# neoPeak.net
KiCad netlist of a schematic drawn in Altium Designer
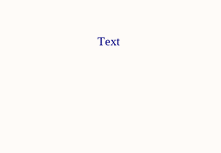
[diagram p0: neoPeak.SchDoc, top middle]
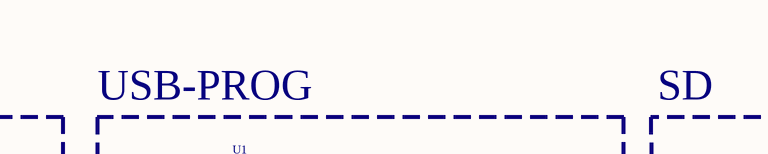
[diagram p1: neoPeak.SchDoc, top right]
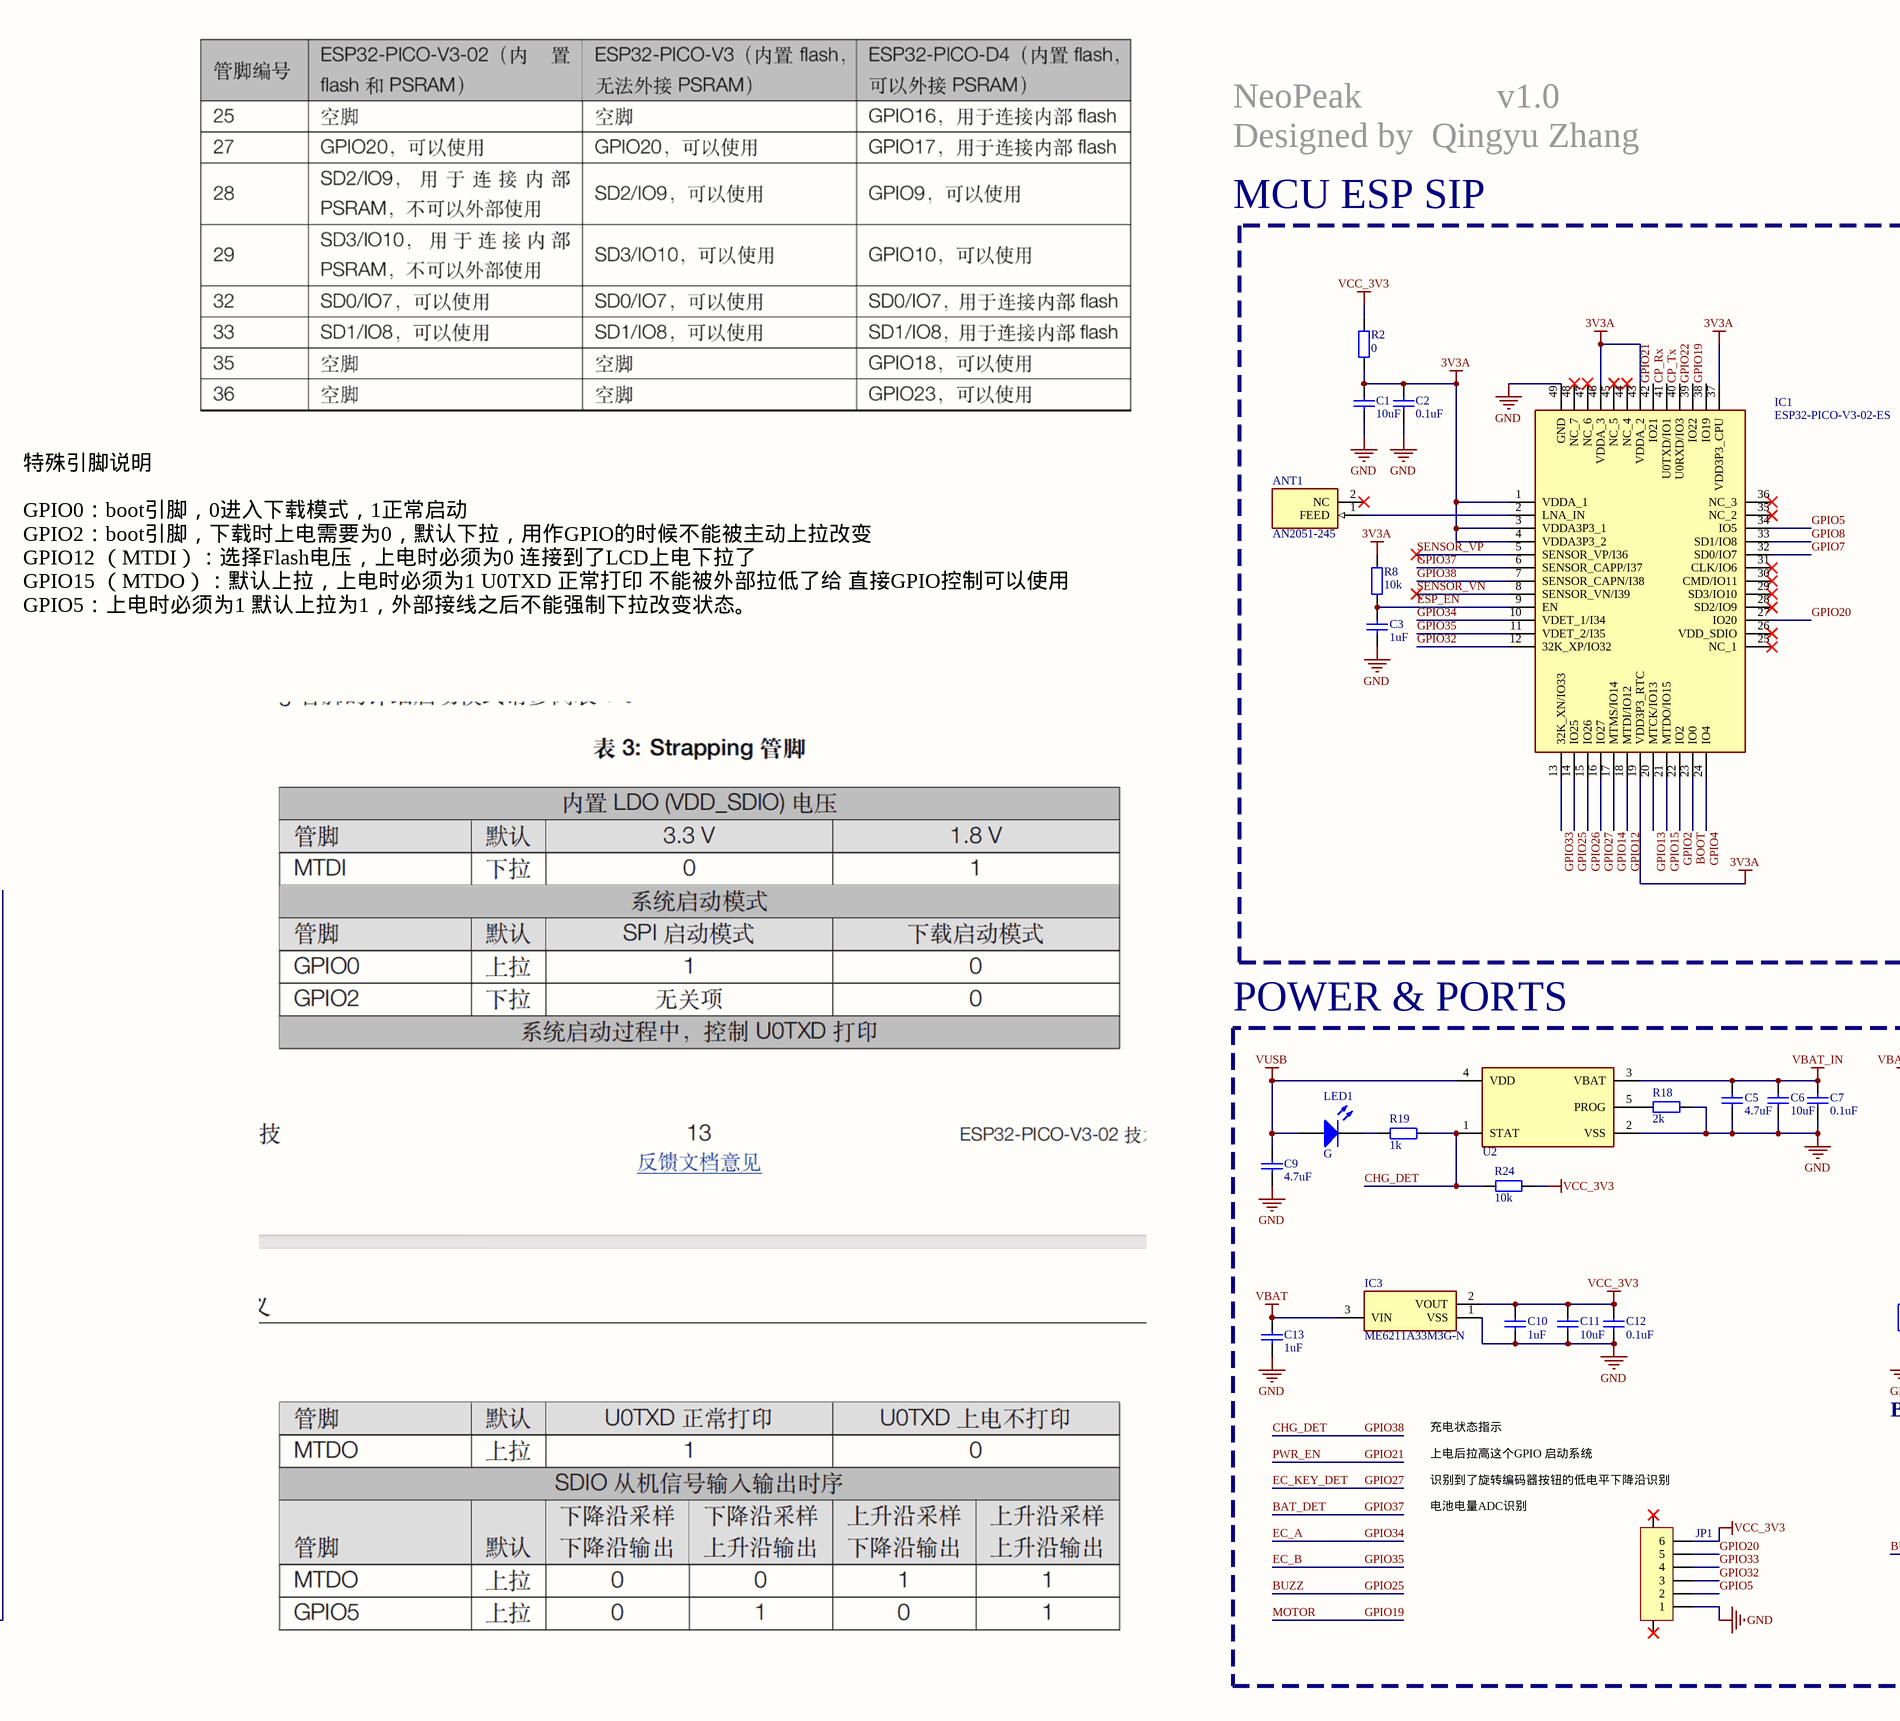
[diagram p2: neoPeak.SchDoc, bottom middle]
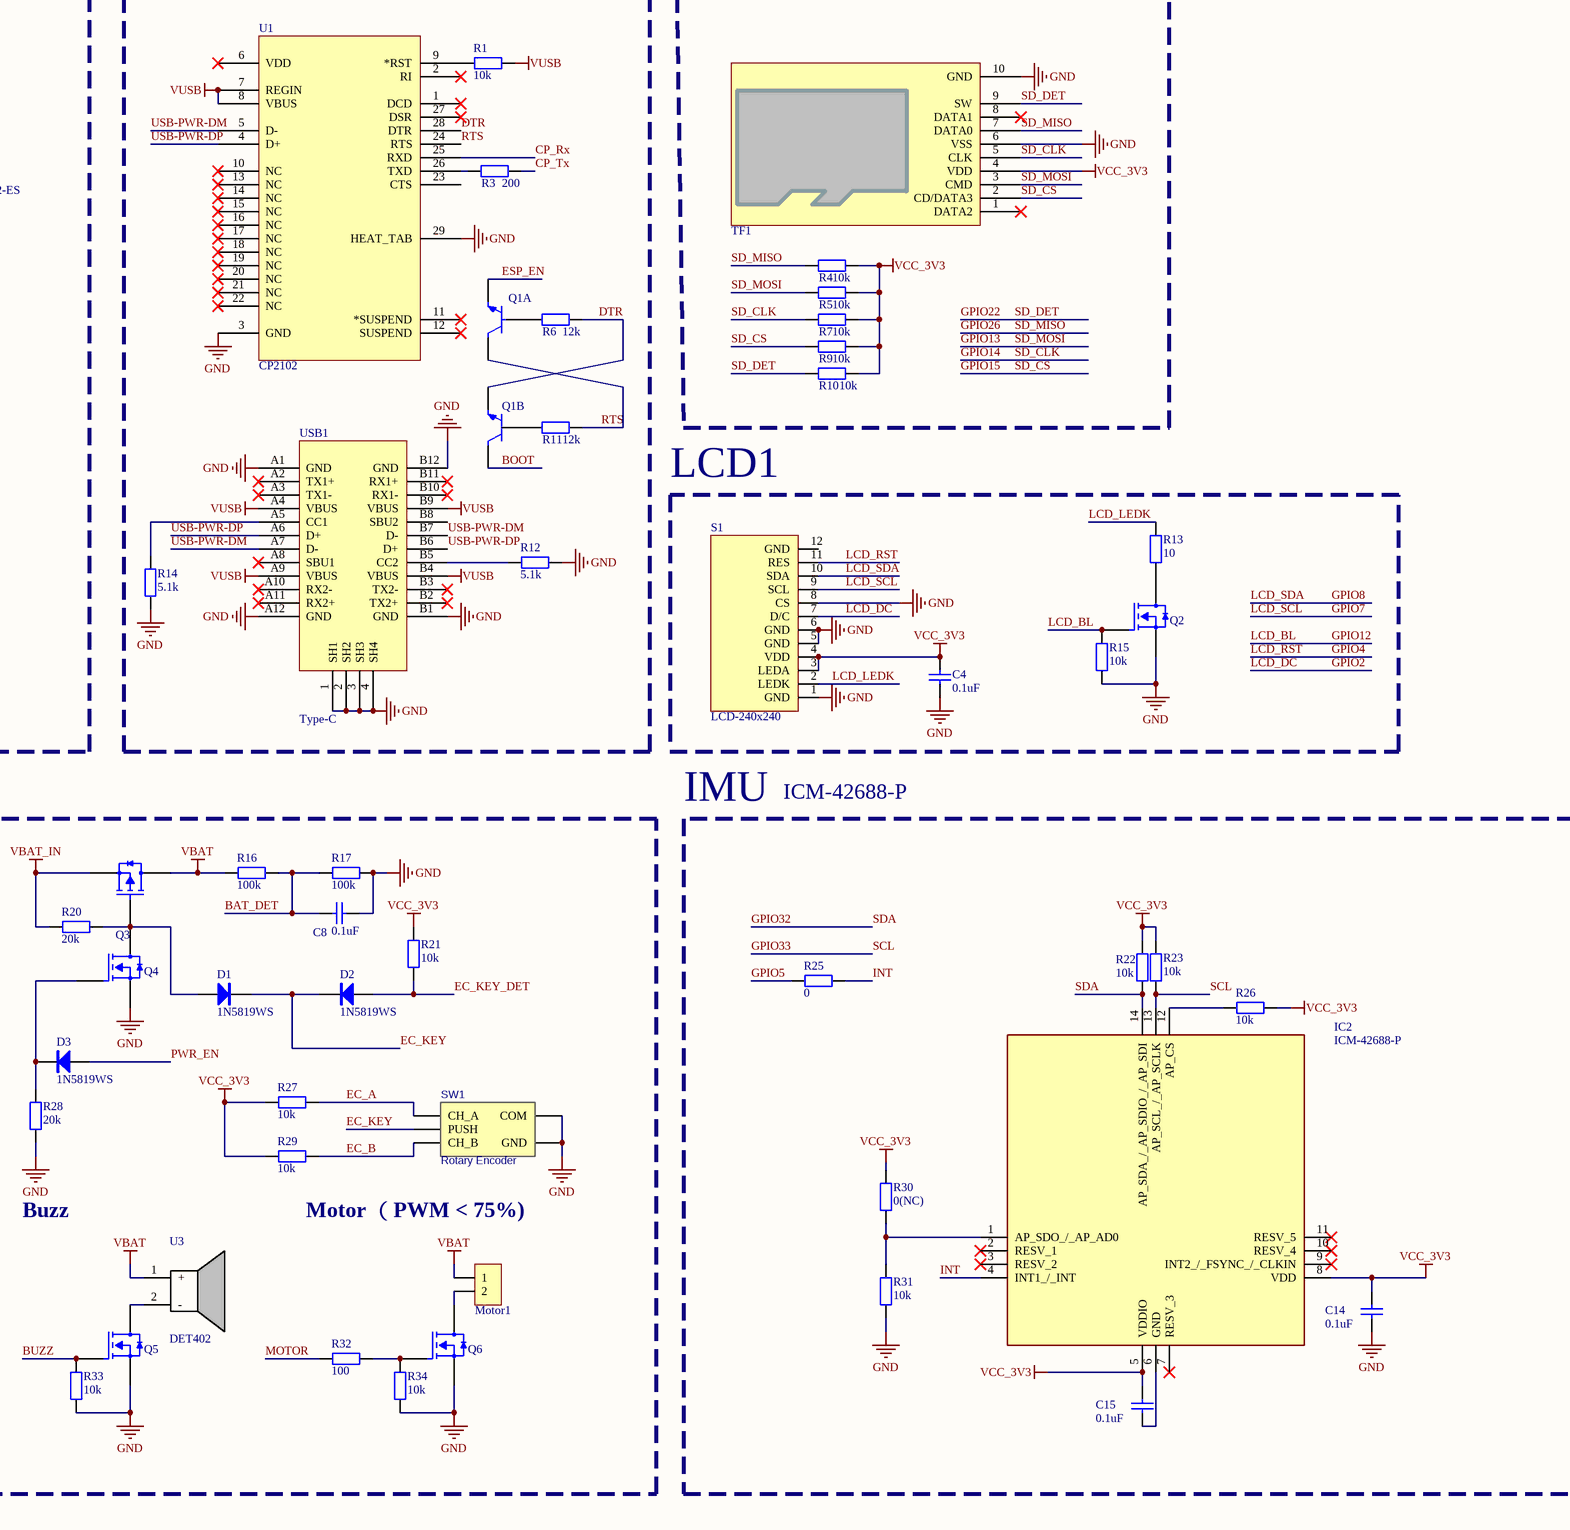
[diagram p3: neoPeak.SchDoc, bottom right]

(export (version "E")
  (design (tool "Eeschema 10.0.6"))
  (components
    (comp (ref "ANT1")
      (value "AN2051-245")
      (footprint "SamacSys:ANTC5020X127N")
      (description "Antenna")
      (libsource (lib "*") (part "AN2051-245"))
    )
    (comp (ref "C1")
      (value "10uF")
      (footprint "C0402_L")
      (description "贴片电容/MLCC电容")
      (libsource (lib "0.1 - 电阻-电容-电感-保险丝-晶振-晶体-磁珠-电位器-法拉电容-馈通电容") (part "C"))
    )
    (comp (ref "C2")
      (value "0.1uF")
      (footprint "C0402_L")
      (description "贴片电容/MLCC电容")
      (libsource (lib "0.1 - 电阻-电容-电感-保险丝-晶振-晶体-磁珠-电位器-法拉电容-馈通电容") (part "C"))
    )
    (comp (ref "C3")
      (value "1uF")
      (footprint "C0402_L")
      (description "贴片电容/MLCC电容")
      (libsource (lib "0.1 - 电阻-电容-电感-保险丝-晶振-晶体-磁珠-电位器-法拉电容-馈通电容") (part "C"))
    )
    (comp (ref "C4")
      (value "0.1uF")
      (footprint "C0402_L")
      (description "贴片电容/MLCC电容")
      (libsource (lib "0.1 - 电阻-电容-电感-保险丝-晶振-晶体-磁珠-电位器-法拉电容-馈通电容") (part "C"))
    )
    (comp (ref "C5")
      (value "4.7uF")
      (footprint "C0402_L")
      (description "贴片电容/MLCC电容")
      (libsource (lib "0.1 - 电阻-电容-电感-保险丝-晶振-晶体-磁珠-电位器-法拉电容-馈通电容") (part "C"))
    )
    (comp (ref "C6")
      (value "10uF")
      (footprint "C0402_L")
      (description "贴片电容/MLCC电容")
      (libsource (lib "0.1 - 电阻-电容-电感-保险丝-晶振-晶体-磁珠-电位器-法拉电容-馈通电容") (part "C"))
    )
    (comp (ref "C7")
      (value "0.1uF")
      (footprint "C0402_L")
      (description "贴片电容/MLCC电容")
      (libsource (lib "0.1 - 电阻-电容-电感-保险丝-晶振-晶体-磁珠-电位器-法拉电容-馈通电容") (part "C"))
    )
    (comp (ref "C8")
      (value "0.1uF")
      (footprint "C0402_L")
      (description "贴片电容/MLCC电容")
      (libsource (lib "0.1 - 电阻-电容-电感-保险丝-晶振-晶体-磁珠-电位器-法拉电容-馈通电容") (part "C"))
    )
    (comp (ref "C9")
      (value "4.7uF")
      (footprint "C0402_L")
      (description "贴片电容/MLCC电容")
      (libsource (lib "0.1 - 电阻-电容-电感-保险丝-晶振-晶体-磁珠-电位器-法拉电容-馈通电容") (part "C"))
    )
    (comp (ref "C10")
      (value "1uF")
      (footprint "C0402_L")
      (description "贴片电容/MLCC电容")
      (libsource (lib "0.1 - 电阻-电容-电感-保险丝-晶振-晶体-磁珠-电位器-法拉电容-馈通电容") (part "C"))
    )
    (comp (ref "C11")
      (value "10uF")
      (footprint "C0402_L")
      (description "贴片电容/MLCC电容")
      (libsource (lib "0.1 - 电阻-电容-电感-保险丝-晶振-晶体-磁珠-电位器-法拉电容-馈通电容") (part "C"))
    )
    (comp (ref "C12")
      (value "0.1uF")
      (footprint "C0402_L")
      (description "贴片电容/MLCC电容")
      (libsource (lib "0.1 - 电阻-电容-电感-保险丝-晶振-晶体-磁珠-电位器-法拉电容-馈通电容") (part "C"))
    )
    (comp (ref "C13")
      (value "1uF")
      (footprint "C0402_L")
      (description "贴片电容/MLCC电容")
      (libsource (lib "0.1 - 电阻-电容-电感-保险丝-晶振-晶体-磁珠-电位器-法拉电容-馈通电容") (part "C"))
    )
    (comp (ref "C14")
      (value "0.1uF")
      (footprint "C0402_L")
      (description "贴片电容/MLCC电容")
      (libsource (lib "0.1 - 电阻-电容-电感-保险丝-晶振-晶体-磁珠-电位器-法拉电容-馈通电容") (part "C"))
    )
    (comp (ref "C15")
      (value "0.1uF")
      (footprint "C0402_L")
      (description "贴片电容/MLCC电容")
      (libsource (lib "0.1 - 电阻-电容-电感-保险丝-晶振-晶体-磁珠-电位器-法拉电容-馈通电容") (part "C"))
    )
    (comp (ref "D1")
      (value "1N5819WS")
      (footprint "SOD-323")
      (description "肖特基二极管")
      (fields (field (name "版权归属") "源创客"))
      (libsource (lib "8.1   - 二极管-整流桥") (part "1N5819"))
    )
    (comp (ref "D2")
      (value "1N5819WS")
      (footprint "SOD-323")
      (description "肖特基二极管")
      (fields (field (name "版权归属") "源创客"))
      (libsource (lib "8.1   - 二极管-整流桥") (part "1N5819"))
    )
    (comp (ref "D3")
      (value "1N5819WS")
      (footprint "SOD-323")
      (description "肖特基二极管")
      (fields (field (name "版权归属") "源创客"))
      (libsource (lib "8.1   - 二极管-整流桥") (part "1N5819"))
    )
    (comp (ref "IC1")
      (value "ESP32-PICO-V3-02-ES")
      (footprint "SamacSys:ESP32PICOV302ES")
      (description "Integrated Circuit")
      (libsource (lib "SamacSys") (part "ESP32-PICO-V3-02-ES"))
    )
    (comp (ref "IC2")
      (value "ICM-42688-P")
      (footprint "SamacSys:IIM42352")
      (description "Integrated Circuit")
      (fields (field (name "MOUSER PART NUMBER") "410-ICM-42688-P"))
      (libsource (lib "SamacSys") (part "ICM-42688-P"))
    )
    (comp (ref "IC3")
      (value "ME6211A33M3G-N")
      (footprint "SamacSys:SOT95P280X145-3N")
      (description "Integrated Circuit")
      (libsource (lib "*") (part "ME6211A33M3G-N"))
    )
    (comp (ref "JP1")
      (value "CON-6P")
      (footprint "FPC0.5-WT-6P")
      (description "6P连接器")
      (libsource (lib "4.9 - 0.5mm连接器(FPC0.5)") (part "Header 6"))
    )
    (comp (ref "LED1")
      (value "G")
      (footprint "LED0402_G")
      (description "贴片LED")
      (libsource (lib "0.3 - LED发光二极管-IR二极管_接收管-光耦") (part "LED"))
    )
    (comp (ref "Motor1")
      (value "HDR-1X2")
      (footprint "HDR1.27-LI-2P")
      (description "2P连接器")
      (libsource (lib "5.2 - 1.27mm连接器(1.27排针排母)") (part "Header 2"))
    )
    (comp (ref "Q1") (value "BC847BVC-7") (footprint "SOT563-6") (libsource (lib "Peak") (part "BC847BVC-7")))
    (comp (ref "Q2")
      (value "AO3400A")
      (footprint "SOT23-3")
      (description "N-MOS")
      (libsource (lib "Peak") (part "AO3400A"))
    )
    (comp (ref "Q3")
      (value "AO3401A")
      (footprint "SOT23-3")
      (description "P-MOS")
      (libsource (lib "Peak") (part "AO3401A"))
    )
    (comp (ref "Q4")
      (value "AO3400A")
      (footprint "SOT23-3")
      (description "N-MOS")
      (libsource (lib "Peak") (part "AO3400A"))
    )
    (comp (ref "Q5")
      (value "AO3400A")
      (footprint "SOT23-3")
      (description "N-MOS")
      (libsource (lib "Peak") (part "AO3400A"))
    )
    (comp (ref "Q6")
      (value "AO3400A")
      (footprint "SOT23-3")
      (description "N-MOS")
      (libsource (lib "Peak") (part "AO3400A"))
    )
    (comp (ref "R1")
      (value "10k")
      (footprint "R0402_L")
      (description "贴片电阻")
      (libsource (lib "0.1 - 电阻-电容-电感-保险丝-晶振-晶体-磁珠-电位器-法拉电容-馈通电容") (part "R"))
    )
    (comp (ref "R2")
      (value "0")
      (footprint "R0402_L")
      (description "贴片电阻")
      (libsource (lib "0.1 - 电阻-电容-电感-保险丝-晶振-晶体-磁珠-电位器-法拉电容-馈通电容") (part "R"))
    )
    (comp (ref "R3")
      (value "200")
      (footprint "R0402_L")
      (description "贴片电阻")
      (libsource (lib "0.1 - 电阻-电容-电感-保险丝-晶振-晶体-磁珠-电位器-法拉电容-馈通电容") (part "R"))
    )
    (comp (ref "R4")
      (value "10k")
      (footprint "R0402_L")
      (description "贴片电阻")
      (libsource (lib "0.1 - 电阻-电容-电感-保险丝-晶振-晶体-磁珠-电位器-法拉电容-馈通电容") (part "R"))
    )
    (comp (ref "R5")
      (value "10k")
      (footprint "R0402_L")
      (description "贴片电阻")
      (libsource (lib "0.1 - 电阻-电容-电感-保险丝-晶振-晶体-磁珠-电位器-法拉电容-馈通电容") (part "R"))
    )
    (comp (ref "R6")
      (value "12k")
      (footprint "R0402_L")
      (description "贴片电阻")
      (libsource (lib "0.1 - 电阻-电容-电感-保险丝-晶振-晶体-磁珠-电位器-法拉电容-馈通电容") (part "R"))
    )
    (comp (ref "R7")
      (value "10k")
      (footprint "R0402_L")
      (description "贴片电阻")
      (libsource (lib "0.1 - 电阻-电容-电感-保险丝-晶振-晶体-磁珠-电位器-法拉电容-馈通电容") (part "R"))
    )
    (comp (ref "R8")
      (value "10k")
      (footprint "R0402_L")
      (description "贴片电阻")
      (libsource (lib "0.1 - 电阻-电容-电感-保险丝-晶振-晶体-磁珠-电位器-法拉电容-馈通电容") (part "R"))
    )
    (comp (ref "R9")
      (value "10k")
      (footprint "R0402_L")
      (description "贴片电阻")
      (libsource (lib "0.1 - 电阻-电容-电感-保险丝-晶振-晶体-磁珠-电位器-法拉电容-馈通电容") (part "R"))
    )
    (comp (ref "R10")
      (value "10k")
      (footprint "R0402_L")
      (description "贴片电阻")
      (libsource (lib "0.1 - 电阻-电容-电感-保险丝-晶振-晶体-磁珠-电位器-法拉电容-馈通电容") (part "R"))
    )
    (comp (ref "R11")
      (value "12k")
      (footprint "R0402_L")
      (description "贴片电阻")
      (libsource (lib "0.1 - 电阻-电容-电感-保险丝-晶振-晶体-磁珠-电位器-法拉电容-馈通电容") (part "R"))
    )
    (comp (ref "R12")
      (value "5.1k")
      (footprint "R0402_L")
      (description "贴片电阻")
      (libsource (lib "0.1 - 电阻-电容-电感-保险丝-晶振-晶体-磁珠-电位器-法拉电容-馈通电容") (part "R"))
    )
    (comp (ref "R13")
      (value "10")
      (footprint "R0402_L")
      (description "贴片电阻")
      (libsource (lib "0.1 - 电阻-电容-电感-保险丝-晶振-晶体-磁珠-电位器-法拉电容-馈通电容") (part "R"))
    )
    (comp (ref "R14")
      (value "5.1k")
      (footprint "R0402_L")
      (description "贴片电阻")
      (libsource (lib "0.1 - 电阻-电容-电感-保险丝-晶振-晶体-磁珠-电位器-法拉电容-馈通电容") (part "R"))
    )
    (comp (ref "R15")
      (value "10k")
      (footprint "R0402_L")
      (description "贴片电阻")
      (libsource (lib "0.1 - 电阻-电容-电感-保险丝-晶振-晶体-磁珠-电位器-法拉电容-馈通电容") (part "R"))
    )
    (comp (ref "R16")
      (value "100k")
      (footprint "R0402_L")
      (description "贴片电阻")
      (libsource (lib "0.1 - 电阻-电容-电感-保险丝-晶振-晶体-磁珠-电位器-法拉电容-馈通电容") (part "R"))
    )
    (comp (ref "R17")
      (value "100k")
      (footprint "R0402_L")
      (description "贴片电阻")
      (libsource (lib "0.1 - 电阻-电容-电感-保险丝-晶振-晶体-磁珠-电位器-法拉电容-馈通电容") (part "R"))
    )
    (comp (ref "R18")
      (value "2k")
      (footprint "R0402_L")
      (description "贴片电阻")
      (libsource (lib "0.1 - 电阻-电容-电感-保险丝-晶振-晶体-磁珠-电位器-法拉电容-馈通电容") (part "R"))
    )
    (comp (ref "R19")
      (value "1k")
      (footprint "R0402_L")
      (description "贴片电阻")
      (libsource (lib "0.1 - 电阻-电容-电感-保险丝-晶振-晶体-磁珠-电位器-法拉电容-馈通电容") (part "R"))
    )
    (comp (ref "R20")
      (value "20k")
      (footprint "R0402_L")
      (description "贴片电阻")
      (libsource (lib "0.1 - 电阻-电容-电感-保险丝-晶振-晶体-磁珠-电位器-法拉电容-馈通电容") (part "R"))
    )
    (comp (ref "R21")
      (value "10k")
      (footprint "R0402_L")
      (description "贴片电阻")
      (libsource (lib "0.1 - 电阻-电容-电感-保险丝-晶振-晶体-磁珠-电位器-法拉电容-馈通电容") (part "R"))
    )
    (comp (ref "R22")
      (value "10k")
      (footprint "R0402_L")
      (description "贴片电阻")
      (libsource (lib "0.1 - 电阻-电容-电感-保险丝-晶振-晶体-磁珠-电位器-法拉电容-馈通电容") (part "R"))
    )
    (comp (ref "R23")
      (value "10k")
      (footprint "R0402_L")
      (description "贴片电阻")
      (libsource (lib "0.1 - 电阻-电容-电感-保险丝-晶振-晶体-磁珠-电位器-法拉电容-馈通电容") (part "R"))
    )
    (comp (ref "R24")
      (value "10k")
      (footprint "R0402_L")
      (description "贴片电阻")
      (libsource (lib "0.1 - 电阻-电容-电感-保险丝-晶振-晶体-磁珠-电位器-法拉电容-馈通电容") (part "R"))
    )
    (comp (ref "R25")
      (value "0")
      (footprint "R0402_L")
      (description "贴片电阻")
      (libsource (lib "0.1 - 电阻-电容-电感-保险丝-晶振-晶体-磁珠-电位器-法拉电容-馈通电容") (part "R"))
    )
    (comp (ref "R26")
      (value "10k")
      (footprint "R0402_L")
      (description "贴片电阻")
      (libsource (lib "0.1 - 电阻-电容-电感-保险丝-晶振-晶体-磁珠-电位器-法拉电容-馈通电容") (part "R"))
    )
    (comp (ref "R27")
      (value "10k")
      (footprint "R0402_L")
      (description "贴片电阻")
      (libsource (lib "0.1 - 电阻-电容-电感-保险丝-晶振-晶体-磁珠-电位器-法拉电容-馈通电容") (part "R"))
    )
    (comp (ref "R28")
      (value "20k")
      (footprint "R0402_L")
      (description "贴片电阻")
      (libsource (lib "0.1 - 电阻-电容-电感-保险丝-晶振-晶体-磁珠-电位器-法拉电容-馈通电容") (part "R"))
    )
    (comp (ref "R29")
      (value "10k")
      (footprint "R0402_L")
      (description "贴片电阻")
      (libsource (lib "0.1 - 电阻-电容-电感-保险丝-晶振-晶体-磁珠-电位器-法拉电容-馈通电容") (part "R"))
    )
    (comp (ref "R30")
      (value "0(NC)")
      (footprint "R0402_L")
      (description "贴片电阻")
      (libsource (lib "0.1 - 电阻-电容-电感-保险丝-晶振-晶体-磁珠-电位器-法拉电容-馈通电容") (part "R"))
    )
    (comp (ref "R31")
      (value "10k")
      (footprint "R0402_L")
      (description "贴片电阻")
      (libsource (lib "0.1 - 电阻-电容-电感-保险丝-晶振-晶体-磁珠-电位器-法拉电容-馈通电容") (part "R"))
    )
    (comp (ref "R32")
      (value "100")
      (footprint "R0402_L")
      (description "贴片电阻")
      (libsource (lib "0.1 - 电阻-电容-电感-保险丝-晶振-晶体-磁珠-电位器-法拉电容-馈通电容") (part "R"))
    )
    (comp (ref "R33")
      (value "10k")
      (footprint "R0402_L")
      (description "贴片电阻")
      (libsource (lib "0.1 - 电阻-电容-电感-保险丝-晶振-晶体-磁珠-电位器-法拉电容-馈通电容") (part "R"))
    )
    (comp (ref "R34")
      (value "10k")
      (footprint "R0402_L")
      (description "贴片电阻")
      (libsource (lib "0.1 - 电阻-电容-电感-保险丝-晶振-晶体-磁珠-电位器-法拉电容-馈通电容") (part "R"))
    )
    (comp (ref "S1")
      (value "LCD-240x240")
      (footprint "LCD-240x240-FlUSH-154")
      (description "显示屏")
      (libsource (lib "mLib") (part "LCD-240x240"))
    )
    (comp (ref "SW1")
      (value "Rotary Encoder")
      (footprint "SIQ-02FVS3")
      (fields
        (field (name "BOM_SUPPLIER PART") "C1322543")
        (field (name "BOM_MANUFACTURER PART") "EC11E1534443")
        (field (name "CONTRIBUTOR") "LCSC")
      )
      (libsource (lib "Peak") (part "Rotary Encoder"))
    )
    (comp (ref "TF1")
      (value "TF")
      (footprint "TF-SOCKET")
      (description "8脚自弹")
      (libsource (lib "Peak") (part "TF卡座"))
    )
    (comp (ref "U1")
      (value "CP2102")
      (footprint "QFN-28")
      (description "USB转TTL")
      (libsource (lib "mLib") (part "CP2102"))
    )
    (comp (ref "U2") (value "MCP73831T") (footprint "SOT23-5") (libsource (lib "Peak") (part "MCP73831T")))
    (comp (ref "U3") (value "DET402") (footprint "DET402") (libsource (lib "Peak") (part "DET402")))
    (comp (ref "USB1")
      (value "Type-C")
      (footprint "Type-C-TOP")
      (libsource (lib "Peak") (part "USB-Type-C-TOP"))
    )
  )
  (nets
    (net (code "1") (name "/BAT_DET") (class "Default")
      (node (ref "C8") (pin "1") (pinfunction "1_1") (pintype "passive"))
      (node (ref "IC1") (pin "6") (pinfunction "SENSOR_CAPP/I37_6") (pintype "passive"))
      (node (ref "R16") (pin "2") (pinfunction "2_2") (pintype "passive"))
      (node (ref "R17") (pin "1") (pinfunction "1_1") (pintype "passive"))
    )
    (net (code "2") (name "/BOOT") (class "Default")
      (node (ref "IC1") (pin "23") (pinfunction "IO0_23") (pintype "passive"))
      (node (ref "Q1") (pin "3") (pinfunction "C2_3") (pintype "passive"))
    )
    (net (code "3") (name "/BUZZ") (class "Default")
      (node (ref "IC1") (pin "14") (pinfunction "IO25_14") (pintype "passive"))
      (node (ref "Q5") (pin "1") (pinfunction "G_1") (pintype "passive"))
      (node (ref "R33") (pin "1") (pinfunction "1_1") (pintype "passive"))
    )
    (net (code "4") (name "/CHG_DET") (class "Default")
      (node (ref "IC1") (pin "7") (pinfunction "SENSOR_CAPN/I38_7") (pintype "passive"))
      (node (ref "R19") (pin "2") (pinfunction "2_2") (pintype "passive"))
      (node (ref "R24") (pin "1") (pinfunction "1_1") (pintype "passive"))
      (node (ref "U2") (pin "1") (pinfunction "STAT_1") (pintype "passive"))
    )
    (net (code "5") (name "/CP_Rx") (class "Default")
      (node (ref "IC1") (pin "41") (pinfunction "U0TXD/IO1_41") (pintype "passive"))
      (node (ref "U1") (pin "25") (pinfunction "RXD_25") (pintype "passive"))
    )
    (net (code "6") (name "/CP_Tx") (class "Default")
      (node (ref "IC1") (pin "40") (pinfunction "U0RXD/IO3_40") (pintype "passive"))
      (node (ref "R3") (pin "1") (pinfunction "1_1") (pintype "passive"))
    )
    (net (code "7") (name "/DTR") (class "Default")
      (node (ref "Q1") (pin "4") (pinfunction "E2_4") (pintype "passive"))
      (node (ref "R6") (pin "1") (pinfunction "1_1") (pintype "passive"))
      (node (ref "U1") (pin "28") (pinfunction "DTR_28") (pintype "passive"))
    )
    (net (code "8") (name "/EC_A") (class "Default")
      (node (ref "IC1") (pin "10") (pinfunction "VDET_1/I34_10") (pintype "passive"))
      (node (ref "R27") (pin "2") (pinfunction "2_2") (pintype "passive"))
      (node (ref "SW1") (pin "1") (pinfunction "CH_A_1") (pintype "passive"))
    )
    (net (code "9") (name "/EC_B") (class "Default")
      (node (ref "IC1") (pin "11") (pinfunction "VDET_2/I35_11") (pintype "passive"))
      (node (ref "R29") (pin "2") (pinfunction "2_2") (pintype "passive"))
      (node (ref "SW1") (pin "4") (pinfunction "CH_B_4") (pintype "passive"))
    )
    (net (code "10") (name "/EC_KEY") (class "Default")
      (node (ref "D1") (pin "2") (pinfunction "K_2") (pintype "passive"))
      (node (ref "D2") (pin "2") (pinfunction "K_2") (pintype "passive"))
      (node (ref "SW1") (pin "2") (pinfunction "PUSH_2") (pintype "passive"))
    )
    (net (code "11") (name "/EC_KEY_DET") (class "Default")
      (node (ref "D2") (pin "1") (pinfunction "A_1") (pintype "passive"))
      (node (ref "IC1") (pin "16") (pinfunction "IO27_16") (pintype "passive"))
      (node (ref "R21") (pin "1") (pinfunction "1_1") (pintype "passive"))
    )
    (net (code "12") (name "/ESP_EN") (class "Default")
      (node (ref "C3") (pin "2") (pinfunction "2_2") (pintype "passive"))
      (node (ref "IC1") (pin "9") (pinfunction "EN_9") (pintype "passive"))
      (node (ref "Q1") (pin "1") (pinfunction "E1_1") (pintype "passive"))
      (node (ref "R8") (pin "1") (pinfunction "1_1") (pintype "passive"))
    )
    (net (code "13") (name "/GPIO2") (class "Default")
      (node (ref "IC1") (pin "22") (pinfunction "IO2_22") (pintype "passive"))
      (node (ref "S1") (pin "7") (pinfunction "D/C_7") (pintype "passive"))
    )
    (net (code "14") (name "/GPIO4") (class "Default")
      (node (ref "IC1") (pin "24") (pinfunction "IO4_24") (pintype "passive"))
      (node (ref "S1") (pin "11") (pinfunction "RES_11") (pintype "passive"))
    )
    (net (code "15") (name "/GPIO5") (class "Default")
      (node (ref "IC1") (pin "34") (pinfunction "IO5_34") (pintype "passive"))
      (node (ref "JP1") (pin "2") (pinfunction "2_2") (pintype "passive"))
      (node (ref "R25") (pin "2") (pinfunction "2_2") (pintype "passive"))
    )
    (net (code "16") (name "/GPIO7") (class "Default")
      (node (ref "IC1") (pin "32") (pinfunction "SD0/IO7_32") (pintype "passive"))
      (node (ref "S1") (pin "9") (pinfunction "SCL_9") (pintype "passive"))
    )
    (net (code "17") (name "/GPIO8") (class "Default")
      (node (ref "IC1") (pin "33") (pinfunction "SD1/IO8_33") (pintype "passive"))
      (node (ref "S1") (pin "10") (pinfunction "SDA_10") (pintype "passive"))
    )
    (net (code "18") (name "/GPIO12") (class "Default")
      (node (ref "IC1") (pin "18") (pinfunction "MTDI/IO12_18") (pintype "passive"))
      (node (ref "Q2") (pin "1") (pinfunction "G_1") (pintype "passive"))
      (node (ref "R15") (pin "2") (pinfunction "2_2") (pintype "passive"))
    )
    (net (code "19") (name "/GPIO13") (class "Default")
      (node (ref "IC1") (pin "20") (pinfunction "MTCK/IO13_20") (pintype "passive"))
      (node (ref "R5") (pin "2") (pinfunction "2_2") (pintype "passive"))
      (node (ref "TF1") (pin "3") (pinfunction "CMD_3") (pintype "passive"))
    )
    (net (code "20") (name "/GPIO14") (class "Default")
      (node (ref "IC1") (pin "17") (pinfunction "MTMS/IO14_17") (pintype "passive"))
      (node (ref "R7") (pin "2") (pinfunction "2_2") (pintype "passive"))
      (node (ref "TF1") (pin "5") (pinfunction "CLK_5") (pintype "passive"))
    )
    (net (code "21") (name "/GPIO15") (class "Default")
      (node (ref "IC1") (pin "21") (pinfunction "MTDO/IO15_21") (pintype "passive"))
      (node (ref "R9") (pin "2") (pinfunction "2_2") (pintype "passive"))
      (node (ref "TF1") (pin "2") (pinfunction "CD/DATA3_2") (pintype "passive"))
    )
    (net (code "22") (name "/GPIO19") (class "Default")
      (node (ref "IC1") (pin "38") (pinfunction "IO19_38") (pintype "passive"))
      (node (ref "R32") (pin "1") (pinfunction "1_1") (pintype "passive"))
    )
    (net (code "23") (name "/GPIO20") (class "Default")
      (node (ref "IC1") (pin "27") (pinfunction "IO20_27") (pintype "passive"))
      (node (ref "JP1") (pin "5") (pinfunction "5_5") (pintype "passive"))
    )
    (net (code "24") (name "/GPIO21") (class "Default")
      (node (ref "D3") (pin "1") (pinfunction "A_1") (pintype "passive"))
      (node (ref "IC1") (pin "42") (pinfunction "IO21_42") (pintype "passive"))
    )
    (net (code "25") (name "/GPIO22") (class "Default")
      (node (ref "IC1") (pin "39") (pinfunction "IO22_39") (pintype "passive"))
      (node (ref "R10") (pin "2") (pinfunction "2_2") (pintype "passive"))
      (node (ref "TF1") (pin "9") (pinfunction "SW_9") (pintype "passive"))
    )
    (net (code "26") (name "/GPIO26") (class "Default")
      (node (ref "IC1") (pin "15") (pinfunction "IO26_15") (pintype "passive"))
      (node (ref "R4") (pin "2") (pinfunction "2_2") (pintype "passive"))
      (node (ref "TF1") (pin "7") (pinfunction "DATA0_7") (pintype "passive"))
    )
    (net (code "27") (name "/GPIO32") (class "Default")
      (node (ref "IC1") (pin "12") (pinfunction "32K_XP/IO32_12") (pintype "passive"))
      (node (ref "IC2") (pin "14") (pinfunction "AP_SDA_/_AP_SDIO_/_AP_SDI_14") (pintype "passive"))
      (node (ref "JP1") (pin "3") (pinfunction "3_3") (pintype "passive"))
      (node (ref "R22") (pin "2") (pinfunction "2_2") (pintype "passive"))
    )
    (net (code "28") (name "/GPIO33") (class "Default")
      (node (ref "IC1") (pin "13") (pinfunction "32K_XN/IO33_13") (pintype "passive"))
      (node (ref "IC2") (pin "13") (pinfunction "AP_SCL_/_AP_SCLK_13") (pintype "passive"))
      (node (ref "JP1") (pin "4") (pinfunction "4_4") (pintype "passive"))
      (node (ref "R23") (pin "1") (pinfunction "1_1") (pintype "passive"))
    )
    (net (code "29") (name "/INT") (class "Default")
      (node (ref "IC2") (pin "4") (pinfunction "INT1_/_INT_4") (pintype "passive"))
      (node (ref "R25") (pin "1") (pinfunction "1_1") (pintype "passive"))
    )
    (net (code "30") (name "/LCD_LEDK") (class "Default")
      (node (ref "R13") (pin "2") (pinfunction "2_2") (pintype "passive"))
      (node (ref "S1") (pin "2") (pinfunction "LEDK_2") (pintype "passive"))
    )
    (net (code "31") (name "/RTS") (class "Default")
      (node (ref "Q1") (pin "6") (pinfunction "C1_6") (pintype "passive"))
      (node (ref "R11") (pin "1") (pinfunction "1_1") (pintype "passive"))
      (node (ref "U1") (pin "24") (pinfunction "RTS_24") (pintype "passive"))
    )
    (net (code "32") (name "/SENSOR_VN") (class "Default")
      (node (ref "IC1") (pin "8") (pinfunction "SENSOR_VN/I39_8") (pintype "passive+no_connect"))
    )
    (net (code "33") (name "/SENSOR_VP") (class "Default")
      (node (ref "IC1") (pin "5") (pinfunction "SENSOR_VP/I36_5") (pintype "passive+no_connect"))
    )
    (net (code "34") (name "/USB-PWR-DM") (class "Default")
      (node (ref "U1") (pin "5") (pinfunction "D-_5") (pintype "passive"))
      (node (ref "USB1") (pin "A7") (pinfunction "D-_A7") (pintype "passive"))
      (node (ref "USB1") (pin "B7") (pinfunction "D-_B7") (pintype "passive"))
    )
    (net (code "35") (name "/USB-PWR-DP") (class "Default")
      (node (ref "U1") (pin "4") (pinfunction "D+_4") (pintype "passive"))
      (node (ref "USB1") (pin "A6") (pinfunction "D+_A6") (pintype "passive"))
      (node (ref "USB1") (pin "B6") (pinfunction "D+_B6") (pintype "passive"))
    )
    (net (code "36") (name "3V3A") (class "Default")
      (node (ref "C1") (pin "2") (pinfunction "2_2") (pintype "passive"))
      (node (ref "C2") (pin "2") (pinfunction "2_2") (pintype "passive"))
      (node (ref "IC1") (pin "1") (pinfunction "VDDA_1_1") (pintype "passive"))
      (node (ref "IC1") (pin "19") (pinfunction "VDD3P3_RTC_19") (pintype "passive"))
      (node (ref "IC1") (pin "3") (pinfunction "VDDA3P3_1_3") (pintype "passive"))
      (node (ref "IC1") (pin "37") (pinfunction "VDD3P3_CPU_37") (pintype "passive"))
      (node (ref "IC1") (pin "4") (pinfunction "VDDA3P3_2_4") (pintype "passive"))
      (node (ref "IC1") (pin "43") (pinfunction "VDDA_2_43") (pintype "passive"))
      (node (ref "IC1") (pin "46") (pinfunction "VDDA_3_46") (pintype "passive"))
      (node (ref "R2") (pin "1") (pinfunction "1_1") (pintype "passive"))
      (node (ref "R8") (pin "2") (pinfunction "2_2") (pintype "passive"))
    )
    (net (code "37") (name "GND") (class "Default")
      (node (ref "C1") (pin "1") (pinfunction "1_1") (pintype "passive"))
      (node (ref "C10") (pin "1") (pinfunction "1_1") (pintype "passive"))
      (node (ref "C11") (pin "1") (pinfunction "1_1") (pintype "passive"))
      (node (ref "C12") (pin "1") (pinfunction "1_1") (pintype "passive"))
      (node (ref "C13") (pin "1") (pinfunction "1_1") (pintype "passive"))
      (node (ref "C14") (pin "2") (pinfunction "2_2") (pintype "passive"))
      (node (ref "C2") (pin "1") (pinfunction "1_1") (pintype "passive"))
      (node (ref "C3") (pin "1") (pinfunction "1_1") (pintype "passive"))
      (node (ref "C4") (pin "1") (pinfunction "1_1") (pintype "passive"))
      (node (ref "C5") (pin "1") (pinfunction "1_1") (pintype "passive"))
      (node (ref "C6") (pin "1") (pinfunction "1_1") (pintype "passive"))
      (node (ref "C7") (pin "1") (pinfunction "1_1") (pintype "passive"))
      (node (ref "C8") (pin "2") (pinfunction "2_2") (pintype "passive"))
      (node (ref "C9") (pin "1") (pinfunction "1_1") (pintype "passive"))
      (node (ref "IC1") (pin "49") (pinfunction "GND_49") (pintype "passive"))
      (node (ref "IC3") (pin "1") (pinfunction "VSS_1") (pintype "passive"))
      (node (ref "JP1") (pin "1") (pinfunction "1_1") (pintype "passive"))
      (node (ref "Q2") (pin "2") (pinfunction "S_2") (pintype "passive"))
      (node (ref "Q4") (pin "2") (pinfunction "S_2") (pintype "passive"))
      (node (ref "Q5") (pin "2") (pinfunction "S_2") (pintype "passive"))
      (node (ref "Q6") (pin "2") (pinfunction "S_2") (pintype "passive"))
      (node (ref "R12") (pin "1") (pinfunction "1_1") (pintype "passive"))
      (node (ref "R14") (pin "2") (pinfunction "2_2") (pintype "passive"))
      (node (ref "R15") (pin "1") (pinfunction "1_1") (pintype "passive"))
      (node (ref "R17") (pin "2") (pinfunction "2_2") (pintype "passive"))
      (node (ref "R18") (pin "2") (pinfunction "2_2") (pintype "passive"))
      (node (ref "R28") (pin "1") (pinfunction "1_1") (pintype "passive"))
      (node (ref "R31") (pin "2") (pinfunction "2_2") (pintype "passive"))
      (node (ref "R33") (pin "2") (pinfunction "2_2") (pintype "passive"))
      (node (ref "R34") (pin "2") (pinfunction "2_2") (pintype "passive"))
      (node (ref "S1") (pin "1") (pinfunction "GND_1") (pintype "passive"))
      (node (ref "S1") (pin "5") (pinfunction "GND_5") (pintype "passive"))
      (node (ref "S1") (pin "6") (pinfunction "GND_6") (pintype "passive"))
      (node (ref "S1") (pin "8") (pinfunction "CS_8") (pintype "passive"))
      (node (ref "SW1") (pin "3") (pinfunction "COM_3") (pintype "passive"))
      (node (ref "SW1") (pin "5") (pinfunction "GND_5") (pintype "passive"))
      (node (ref "TF1") (pin "10") (pinfunction "GND_10") (pintype "passive"))
      (node (ref "TF1") (pin "6") (pinfunction "VSS_6") (pintype "passive"))
      (node (ref "U1") (pin "29") (pinfunction "HEAT_TAB_29") (pintype "passive"))
      (node (ref "U1") (pin "3") (pinfunction "GND_3") (pintype "passive"))
      (node (ref "U2") (pin "2") (pinfunction "VSS_2") (pintype "power_in"))
      (node (ref "USB1") (pin "1") (pinfunction "SH1_1") (pintype "passive"))
      (node (ref "USB1") (pin "2") (pinfunction "SH2_2") (pintype "passive"))
      (node (ref "USB1") (pin "3") (pinfunction "SH3_3") (pintype "passive"))
      (node (ref "USB1") (pin "4") (pinfunction "SH4_4") (pintype "passive"))
      (node (ref "USB1") (pin "A1") (pinfunction "GND_A1") (pintype "passive"))
      (node (ref "USB1") (pin "A12") (pinfunction "GND_A12") (pintype "passive"))
      (node (ref "USB1") (pin "B1") (pinfunction "GND_B1") (pintype "passive"))
      (node (ref "USB1") (pin "B12") (pinfunction "GND_B12") (pintype "passive"))
    )
    (net (code "38") (name "Net-(ANT1-FEED)") (class "Default")
      (node (ref "ANT1") (pin "1") (pinfunction "FEED_1") (pintype "input"))
      (node (ref "IC1") (pin "2") (pinfunction "LNA_IN_2") (pintype "passive"))
    )
    (net (code "39") (name "Net-(D1-A)") (class "Default")
      (node (ref "D1") (pin "1") (pinfunction "A_1") (pintype "passive"))
      (node (ref "Q3") (pin "1") (pinfunction "G_1") (pintype "passive"))
      (node (ref "Q4") (pin "3") (pinfunction "D_3") (pintype "passive"))
      (node (ref "R20") (pin "2") (pinfunction "2_2") (pintype "passive"))
    )
    (net (code "40") (name "Net-(D3-K)") (class "Default")
      (node (ref "D3") (pin "2") (pinfunction "K_2") (pintype "passive"))
      (node (ref "Q4") (pin "1") (pinfunction "G_1") (pintype "passive"))
      (node (ref "R28") (pin "2") (pinfunction "2_2") (pintype "passive"))
    )
    (net (code "41") (name "Net-(IC2-AP_CS)") (class "Default")
      (node (ref "IC2") (pin "12") (pinfunction "AP_CS_12") (pintype "passive"))
      (node (ref "R26") (pin "2") (pinfunction "2_2") (pintype "passive"))
    )
    (net (code "42") (name "Net-(IC2-AP_SDO_{slash}_AP_AD0)") (class "Default")
      (node (ref "IC2") (pin "1") (pinfunction "AP_SDO_/_AP_AD0_1") (pintype "passive"))
      (node (ref "R30") (pin "2") (pinfunction "2_2") (pintype "passive"))
      (node (ref "R31") (pin "1") (pinfunction "1_1") (pintype "passive"))
    )
    (net (code "43") (name "Net-(IC2-GND)") (class "Default")
      (node (ref "C15") (pin "2") (pinfunction "2_2") (pintype "passive"))
      (node (ref "IC2") (pin "6") (pinfunction "GND_6") (pintype "passive"))
    )
    (net (code "44") (name "Net-(LED1-K)") (class "Default")
      (node (ref "LED1") (pin "2") (pinfunction "K_2") (pintype "passive"))
      (node (ref "R19") (pin "1") (pinfunction "1_1") (pintype "passive"))
    )
    (net (code "45") (name "Net-(Q1A-B1)") (class "Default")
      (node (ref "Q1") (pin "2") (pinfunction "B1_2") (pintype "passive"))
      (node (ref "R6") (pin "2") (pinfunction "2_2") (pintype "passive"))
    )
    (net (code "46") (name "Net-(Q1B-B2)") (class "Default")
      (node (ref "Q1") (pin "5") (pinfunction "B2_5") (pintype "passive"))
      (node (ref "R11") (pin "2") (pinfunction "2_2") (pintype "passive"))
    )
    (net (code "47") (name "Net-(Q2-D)") (class "Default")
      (node (ref "Q2") (pin "3") (pinfunction "D_3") (pintype "passive"))
      (node (ref "R13") (pin "1") (pinfunction "1_1") (pintype "passive"))
    )
    (net (code "48") (name "Net-(Q5-D)") (class "Default")
      (node (ref "Q5") (pin "3") (pinfunction "D_3") (pintype "passive"))
      (node (ref "U3") (pin "2") (pinfunction "-_2") (pintype "passive"))
    )
    (net (code "49") (name "Net-(Q6-D)") (class "Default")
      (node (ref "Motor1") (pin "2") (pinfunction "2_2") (pintype "passive"))
      (node (ref "Q6") (pin "3") (pinfunction "D_3") (pintype "passive"))
    )
    (net (code "50") (name "Net-(Q6-G)") (class "Default")
      (node (ref "Q6") (pin "1") (pinfunction "G_1") (pintype "passive"))
      (node (ref "R32") (pin "2") (pinfunction "2_2") (pintype "passive"))
      (node (ref "R34") (pin "1") (pinfunction "1_1") (pintype "passive"))
    )
    (net (code "51") (name "Net-(U1-*RST)") (class "Default")
      (node (ref "R1") (pin "2") (pinfunction "2_2") (pintype "passive"))
      (node (ref "U1") (pin "9") (pinfunction "*RST_9") (pintype "passive"))
    )
    (net (code "52") (name "Net-(U1-TXD)") (class "Default")
      (node (ref "R3") (pin "2") (pinfunction "2_2") (pintype "passive"))
      (node (ref "U1") (pin "26") (pinfunction "TXD_26") (pintype "passive"))
    )
    (net (code "53") (name "Net-(U2-PROG)") (class "Default")
      (node (ref "R18") (pin "1") (pinfunction "1_1") (pintype "passive"))
      (node (ref "U2") (pin "5") (pinfunction "PROG_5") (pintype "passive"))
    )
    (net (code "54") (name "Net-(USB1-CC1)") (class "Default")
      (node (ref "R14") (pin "1") (pinfunction "1_1") (pintype "passive"))
      (node (ref "USB1") (pin "A5") (pinfunction "CC1_A5") (pintype "passive"))
    )
    (net (code "55") (name "Net-(USB1-CC2)") (class "Default")
      (node (ref "R12") (pin "2") (pinfunction "2_2") (pintype "passive"))
      (node (ref "USB1") (pin "B5") (pinfunction "CC2_B5") (pintype "passive"))
    )
    (net (code "56") (name "VBAT") (class "Default")
      (node (ref "C13") (pin "2") (pinfunction "2_2") (pintype "passive"))
      (node (ref "IC3") (pin "3") (pinfunction "VIN_3") (pintype "passive"))
      (node (ref "Motor1") (pin "1") (pinfunction "1_1") (pintype "passive"))
      (node (ref "Q3") (pin "3") (pinfunction "D_3") (pintype "passive"))
      (node (ref "R16") (pin "1") (pinfunction "1_1") (pintype "passive"))
      (node (ref "U3") (pin "1") (pinfunction "+_1") (pintype "passive"))
    )
    (net (code "57") (name "VBAT_IN") (class "Default")
      (node (ref "C5") (pin "2") (pinfunction "2_2") (pintype "passive"))
      (node (ref "C6") (pin "2") (pinfunction "2_2") (pintype "passive"))
      (node (ref "C7") (pin "2") (pinfunction "2_2") (pintype "passive"))
      (node (ref "Q3") (pin "2") (pinfunction "S_2") (pintype "passive"))
      (node (ref "R20") (pin "1") (pinfunction "1_1") (pintype "passive"))
      (node (ref "U2") (pin "3") (pinfunction "VBAT_3") (pintype "power_in"))
    )
    (net (code "58") (name "VCC_3V3") (class "Default")
      (node (ref "C10") (pin "2") (pinfunction "2_2") (pintype "passive"))
      (node (ref "C11") (pin "2") (pinfunction "2_2") (pintype "passive"))
      (node (ref "C12") (pin "2") (pinfunction "2_2") (pintype "passive"))
      (node (ref "C14") (pin "1") (pinfunction "1_1") (pintype "passive"))
      (node (ref "C15") (pin "1") (pinfunction "1_1") (pintype "passive"))
      (node (ref "C4") (pin "2") (pinfunction "2_2") (pintype "passive"))
      (node (ref "IC2") (pin "5") (pinfunction "VDDIO_5") (pintype "passive"))
      (node (ref "IC2") (pin "8") (pinfunction "VDD_8") (pintype "passive"))
      (node (ref "IC3") (pin "2") (pinfunction "VOUT_2") (pintype "passive"))
      (node (ref "JP1") (pin "6") (pinfunction "6_6") (pintype "passive"))
      (node (ref "R10") (pin "1") (pinfunction "1_1") (pintype "passive"))
      (node (ref "R2") (pin "2") (pinfunction "2_2") (pintype "passive"))
      (node (ref "R21") (pin "2") (pinfunction "2_2") (pintype "passive"))
      (node (ref "R22") (pin "1") (pinfunction "1_1") (pintype "passive"))
      (node (ref "R23") (pin "2") (pinfunction "2_2") (pintype "passive"))
      (node (ref "R24") (pin "2") (pinfunction "2_2") (pintype "passive"))
      (node (ref "R26") (pin "1") (pinfunction "1_1") (pintype "passive"))
      (node (ref "R27") (pin "1") (pinfunction "1_1") (pintype "passive"))
      (node (ref "R29") (pin "1") (pinfunction "1_1") (pintype "passive"))
      (node (ref "R30") (pin "1") (pinfunction "1_1") (pintype "passive"))
      (node (ref "R4") (pin "1") (pinfunction "1_1") (pintype "passive"))
      (node (ref "R5") (pin "1") (pinfunction "1_1") (pintype "passive"))
      (node (ref "R7") (pin "1") (pinfunction "1_1") (pintype "passive"))
      (node (ref "R9") (pin "1") (pinfunction "1_1") (pintype "passive"))
      (node (ref "S1") (pin "3") (pinfunction "LEDA_3") (pintype "passive"))
      (node (ref "S1") (pin "4") (pinfunction "VDD_4") (pintype "passive"))
      (node (ref "TF1") (pin "4") (pinfunction "VDD_4") (pintype "passive"))
    )
    (net (code "59") (name "VUSB") (class "Default")
      (node (ref "C9") (pin "2") (pinfunction "2_2") (pintype "passive"))
      (node (ref "LED1") (pin "1") (pinfunction "A_1") (pintype "passive"))
      (node (ref "R1") (pin "1") (pinfunction "1_1") (pintype "passive"))
      (node (ref "U1") (pin "7") (pinfunction "REGIN_7") (pintype "passive"))
      (node (ref "U1") (pin "8") (pinfunction "VBUS_8") (pintype "passive"))
      (node (ref "U2") (pin "4") (pinfunction "VDD_4") (pintype "power_in"))
      (node (ref "USB1") (pin "A4") (pinfunction "VBUS_A4") (pintype "passive"))
      (node (ref "USB1") (pin "A9") (pinfunction "VBUS_A9") (pintype "passive"))
      (node (ref "USB1") (pin "B4") (pinfunction "VBUS_B4") (pintype "passive"))
      (node (ref "USB1") (pin "B9") (pinfunction "VBUS_B9") (pintype "passive"))
    )
    (net (code "60") (name "unconnected-(ANT1-NC-Pad2)") (class "Default")
      (node (ref "ANT1") (pin "2") (pinfunction "NC_2") (pintype "passive+no_connect"))
    )
    (net (code "61") (name "unconnected-(IC1-CLK{slash}IO6-Pad31)") (class "Default")
      (node (ref "IC1") (pin "31") (pinfunction "CLK/IO6_31") (pintype "passive+no_connect"))
    )
    (net (code "62") (name "unconnected-(IC1-CMD{slash}IO11-Pad30)") (class "Default")
      (node (ref "IC1") (pin "30") (pinfunction "CMD/IO11_30") (pintype "passive+no_connect"))
    )
    (net (code "63") (name "unconnected-(IC1-NC_1-Pad25)") (class "Default")
      (node (ref "IC1") (pin "25") (pinfunction "NC_1_25") (pintype "passive+no_connect"))
    )
    (net (code "64") (name "unconnected-(IC1-NC_2-Pad35)") (class "Default")
      (node (ref "IC1") (pin "35") (pinfunction "NC_2_35") (pintype "passive+no_connect"))
    )
    (net (code "65") (name "unconnected-(IC1-NC_3-Pad36)") (class "Default")
      (node (ref "IC1") (pin "36") (pinfunction "NC_3_36") (pintype "passive+no_connect"))
    )
    (net (code "66") (name "unconnected-(IC1-NC_4-Pad44)") (class "Default")
      (node (ref "IC1") (pin "44") (pinfunction "NC_4_44") (pintype "passive+no_connect"))
    )
    (net (code "67") (name "unconnected-(IC1-NC_5-Pad45)") (class "Default")
      (node (ref "IC1") (pin "45") (pinfunction "NC_5_45") (pintype "passive+no_connect"))
    )
    (net (code "68") (name "unconnected-(IC1-NC_6-Pad47)") (class "Default")
      (node (ref "IC1") (pin "47") (pinfunction "NC_6_47") (pintype "passive+no_connect"))
    )
    (net (code "69") (name "unconnected-(IC1-NC_7-Pad48)") (class "Default")
      (node (ref "IC1") (pin "48") (pinfunction "NC_7_48") (pintype "passive+no_connect"))
    )
    (net (code "70") (name "unconnected-(IC1-SD2{slash}IO9-Pad28)") (class "Default")
      (node (ref "IC1") (pin "28") (pinfunction "SD2/IO9_28") (pintype "passive+no_connect"))
    )
    (net (code "71") (name "unconnected-(IC1-SD3{slash}IO10-Pad29)") (class "Default")
      (node (ref "IC1") (pin "29") (pinfunction "SD3/IO10_29") (pintype "passive+no_connect"))
    )
    (net (code "72") (name "unconnected-(IC1-VDD_SDIO-Pad26)") (class "Default")
      (node (ref "IC1") (pin "26") (pinfunction "VDD_SDIO_26") (pintype "passive+no_connect"))
    )
    (net (code "73") (name "unconnected-(IC2-INT2_{slash}_FSYNC_{slash}_CLKIN-Pad9)") (class "Default")
      (node (ref "IC2") (pin "9") (pinfunction "INT2_/_FSYNC_/_CLKIN_9") (pintype "passive+no_connect"))
    )
    (net (code "74") (name "unconnected-(IC2-RESV_1-Pad2)") (class "Default")
      (node (ref "IC2") (pin "2") (pinfunction "RESV_1_2") (pintype "passive+no_connect"))
    )
    (net (code "75") (name "unconnected-(IC2-RESV_2-Pad3)") (class "Default")
      (node (ref "IC2") (pin "3") (pinfunction "RESV_2_3") (pintype "passive+no_connect"))
    )
    (net (code "76") (name "unconnected-(IC2-RESV_3-Pad7)") (class "Default")
      (node (ref "IC2") (pin "7") (pinfunction "RESV_3_7") (pintype "passive+no_connect"))
    )
    (net (code "77") (name "unconnected-(IC2-RESV_4-Pad10)") (class "Default")
      (node (ref "IC2") (pin "10") (pinfunction "RESV_4_10") (pintype "passive+no_connect"))
    )
    (net (code "78") (name "unconnected-(IC2-RESV_5-Pad11)") (class "Default")
      (node (ref "IC2") (pin "11") (pinfunction "RESV_5_11") (pintype "passive+no_connect"))
    )
    (net (code "79") (name "unconnected-(JP1-Pad0)") (class "Default")
      (node (ref "JP1") (pin "0") (pinfunction "0_0") (pintype "passive+no_connect"))
    )
    (net (code "80") (name "unconnected-(JP1-Pad0)_1") (class "Default")
      (node (ref "JP1") (pin "0") (pinfunction "0_0") (pintype "passive+no_connect"))
    )
    (net (code "81") (name "unconnected-(S1-GND-Pad12)") (class "Default")
      (node (ref "S1") (pin "12") (pinfunction "GND_12") (pintype "passive"))
    )
    (net (code "82") (name "unconnected-(TF1-DATA1-Pad8)") (class "Default")
      (node (ref "TF1") (pin "8") (pinfunction "DATA1_8") (pintype "passive+no_connect"))
    )
    (net (code "83") (name "unconnected-(TF1-DATA2-Pad1)") (class "Default")
      (node (ref "TF1") (pin "1") (pinfunction "DATA2_1") (pintype "passive+no_connect"))
    )
    (net (code "84") (name "unconnected-(U1-*SUSPEND-Pad11)") (class "Default")
      (node (ref "U1") (pin "11") (pinfunction "*SUSPEND_11") (pintype "passive+no_connect"))
    )
    (net (code "85") (name "unconnected-(U1-CTS-Pad23)") (class "Default")
      (node (ref "U1") (pin "23") (pinfunction "CTS_23") (pintype "passive"))
    )
    (net (code "86") (name "unconnected-(U1-DCD-Pad1)") (class "Default")
      (node (ref "U1") (pin "1") (pinfunction "DCD_1") (pintype "passive+no_connect"))
    )
    (net (code "87") (name "unconnected-(U1-DSR-Pad27)") (class "Default")
      (node (ref "U1") (pin "27") (pinfunction "DSR_27") (pintype "passive+no_connect"))
    )
    (net (code "88") (name "unconnected-(U1-NC-Pad10)") (class "Default")
      (node (ref "U1") (pin "10") (pinfunction "NC_10") (pintype "passive+no_connect"))
    )
    (net (code "89") (name "unconnected-(U1-NC-Pad13)") (class "Default")
      (node (ref "U1") (pin "13") (pinfunction "NC_13") (pintype "passive+no_connect"))
    )
    (net (code "90") (name "unconnected-(U1-NC-Pad14)") (class "Default")
      (node (ref "U1") (pin "14") (pinfunction "NC_14") (pintype "passive+no_connect"))
    )
    (net (code "91") (name "unconnected-(U1-NC-Pad15)") (class "Default")
      (node (ref "U1") (pin "15") (pinfunction "NC_15") (pintype "passive+no_connect"))
    )
    (net (code "92") (name "unconnected-(U1-NC-Pad16)") (class "Default")
      (node (ref "U1") (pin "16") (pinfunction "NC_16") (pintype "passive+no_connect"))
    )
    (net (code "93") (name "unconnected-(U1-NC-Pad17)") (class "Default")
      (node (ref "U1") (pin "17") (pinfunction "NC_17") (pintype "passive+no_connect"))
    )
    (net (code "94") (name "unconnected-(U1-NC-Pad18)") (class "Default")
      (node (ref "U1") (pin "18") (pinfunction "NC_18") (pintype "passive+no_connect"))
    )
    (net (code "95") (name "unconnected-(U1-NC-Pad19)") (class "Default")
      (node (ref "U1") (pin "19") (pinfunction "NC_19") (pintype "passive+no_connect"))
    )
    (net (code "96") (name "unconnected-(U1-NC-Pad20)") (class "Default")
      (node (ref "U1") (pin "20") (pinfunction "NC_20") (pintype "passive+no_connect"))
    )
    (net (code "97") (name "unconnected-(U1-NC-Pad21)") (class "Default")
      (node (ref "U1") (pin "21") (pinfunction "NC_21") (pintype "passive+no_connect"))
    )
    (net (code "98") (name "unconnected-(U1-NC-Pad22)") (class "Default")
      (node (ref "U1") (pin "22") (pinfunction "NC_22") (pintype "passive+no_connect"))
    )
    (net (code "99") (name "unconnected-(U1-RI-Pad2)") (class "Default")
      (node (ref "U1") (pin "2") (pinfunction "RI_2") (pintype "passive+no_connect"))
    )
    (net (code "100") (name "unconnected-(U1-SUSPEND-Pad12)") (class "Default")
      (node (ref "U1") (pin "12") (pinfunction "SUSPEND_12") (pintype "passive+no_connect"))
    )
    (net (code "101") (name "unconnected-(U1-VDD-Pad6)") (class "Default")
      (node (ref "U1") (pin "6") (pinfunction "VDD_6") (pintype "passive+no_connect"))
    )
    (net (code "102") (name "unconnected-(USB1-RX1+-PadB11)") (class "Default")
      (node (ref "USB1") (pin "B11") (pinfunction "RX1+_B11") (pintype "passive+no_connect"))
    )
    (net (code "103") (name "unconnected-(USB1-RX1--PadB10)") (class "Default")
      (node (ref "USB1") (pin "B10") (pinfunction "RX1-_B10") (pintype "passive+no_connect"))
    )
    (net (code "104") (name "unconnected-(USB1-RX2+-PadA11)") (class "Default")
      (node (ref "USB1") (pin "A11") (pinfunction "RX2+_A11") (pintype "passive+no_connect"))
    )
    (net (code "105") (name "unconnected-(USB1-RX2--PadA10)") (class "Default")
      (node (ref "USB1") (pin "A10") (pinfunction "RX2-_A10") (pintype "passive+no_connect"))
    )
    (net (code "106") (name "unconnected-(USB1-SBU1-PadA8)") (class "Default")
      (node (ref "USB1") (pin "A8") (pinfunction "SBU1_A8") (pintype "passive+no_connect"))
    )
    (net (code "107") (name "unconnected-(USB1-SBU2-PadB8)") (class "Default")
      (node (ref "USB1") (pin "B8") (pinfunction "SBU2_B8") (pintype "passive"))
    )
    (net (code "108") (name "unconnected-(USB1-TX1+-PadA2)") (class "Default")
      (node (ref "USB1") (pin "A2") (pinfunction "TX1+_A2") (pintype "passive+no_connect"))
    )
    (net (code "109") (name "unconnected-(USB1-TX1--PadA3)") (class "Default")
      (node (ref "USB1") (pin "A3") (pinfunction "TX1-_A3") (pintype "passive+no_connect"))
    )
    (net (code "110") (name "unconnected-(USB1-TX2+-PadB2)") (class "Default")
      (node (ref "USB1") (pin "B2") (pinfunction "TX2+_B2") (pintype "passive+no_connect"))
    )
    (net (code "111") (name "unconnected-(USB1-TX2--PadB3)") (class "Default")
      (node (ref "USB1") (pin "B3") (pinfunction "TX2-_B3") (pintype "passive+no_connect"))
    )
  )
)
